# ni.net
KiCad netlist of a schematic drawn in EAGLE
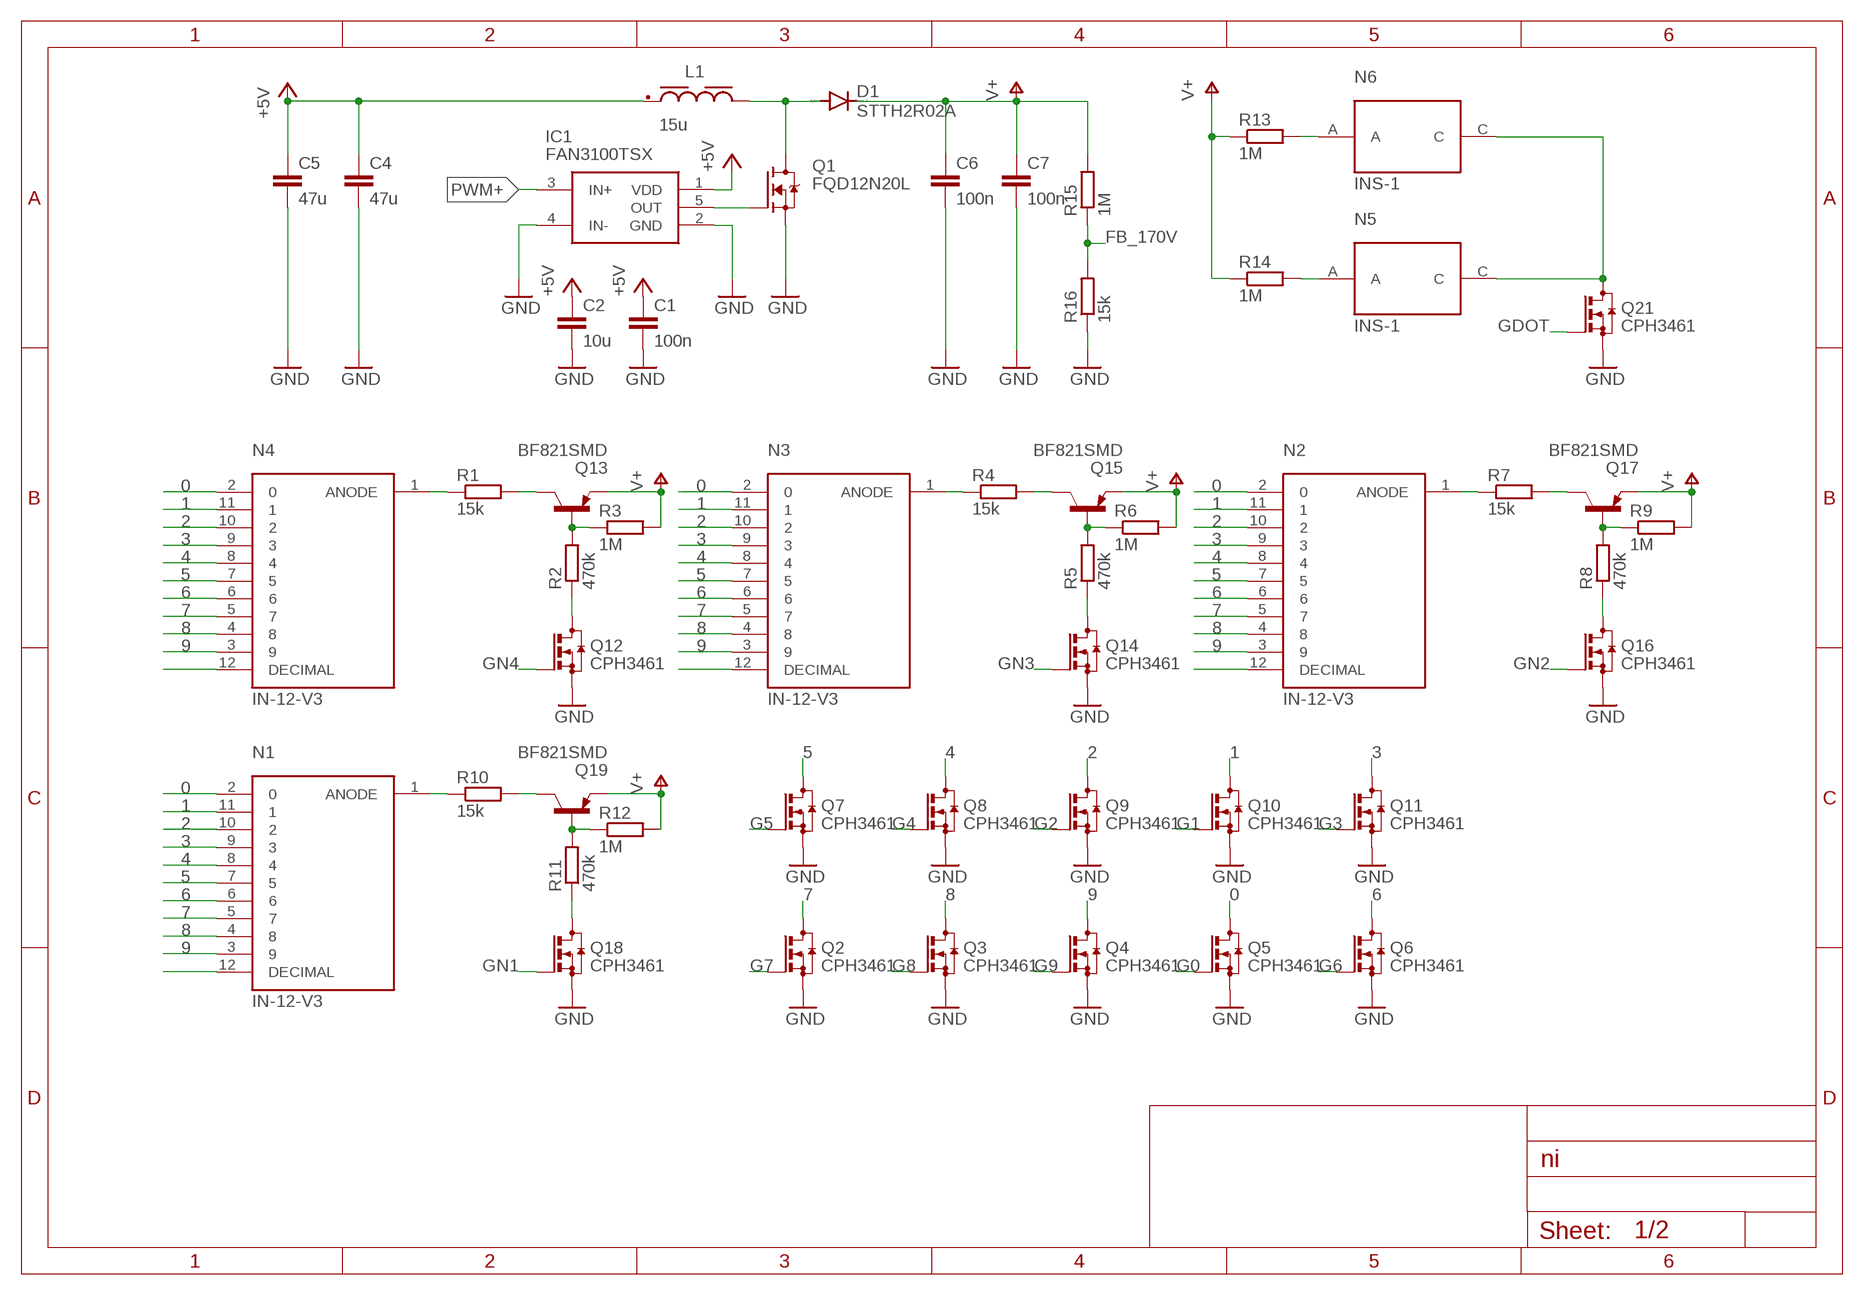
[diagram p0: schematic, sheet 1]
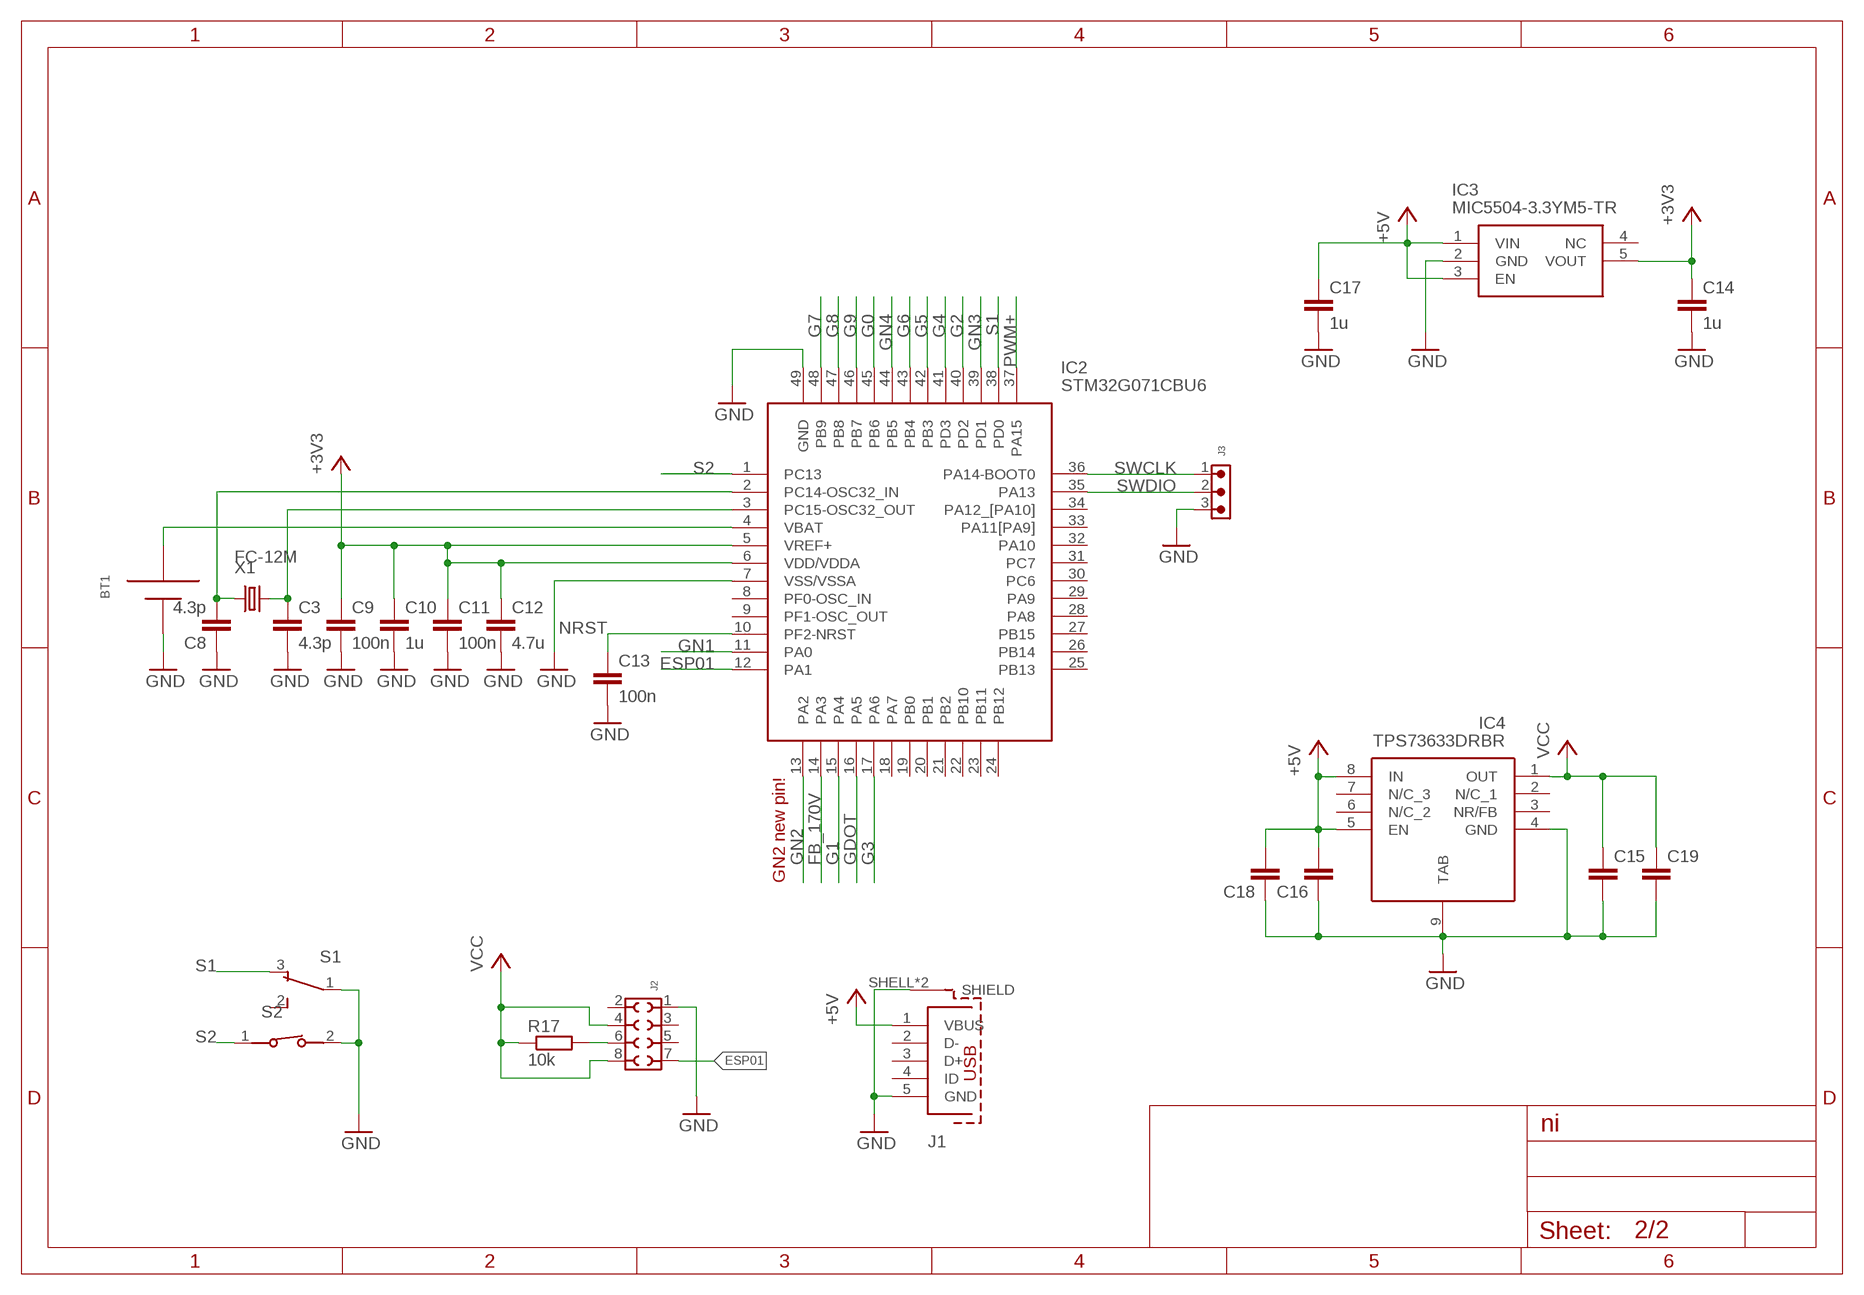
[diagram p1: schematic, sheet 2]

(export (version "E")
  (design (tool "Eeschema 10.0.6"))
  (components
    (comp (ref "C1")
      (value "100n")
      (footprint "eagle-import:C0402")
      (libsource (lib "eagle-import") (part "C-EUC0402"))
    )
    (comp (ref "C2")
      (value "10u")
      (footprint "eagle-import:C1206")
      (libsource (lib "eagle-import") (part "C-EUC1206"))
    )
    (comp (ref "C4")
      (value "47u")
      (footprint "eagle-import:C1206")
      (libsource (lib "eagle-import") (part "C-EUC1206"))
    )
    (comp (ref "C5")
      (value "47u")
      (footprint "eagle-import:C1206")
      (libsource (lib "eagle-import") (part "C-EUC1206"))
    )
    (comp (ref "C6")
      (value "100n")
      (footprint "eagle-import:C1812")
      (libsource (lib "eagle-import") (part "C-EUC1812"))
    )
    (comp (ref "C7")
      (value "100n")
      (footprint "eagle-import:C1812")
      (libsource (lib "eagle-import") (part "C-EUC1812"))
    )
    (comp (ref "D1")
      (value "STTH2R02A")
      (footprint "eagle-import:DO214AC")
      (libsource (lib "eagle-import") (part "DIODE-DO214AC"))
    )
    (comp (ref "IC1")
      (value "FAN3100TSX")
      (footprint "eagle-import:SOT95P280X145-5N")
      (fields (field (name "MOUSER_PART_NUMBER") "512-FAN3100TSX"))
      (libsource (lib "eagle-import") (part "FAN3100TSX"))
    )
    (comp (ref "L1")
      (value "15u")
      (footprint "eagle-import:WE-LQS_5040")
      (libsource (lib "eagle-import") (part "WE-LQS_5040_74404054150"))
    )
    (comp (ref "N1")
      (value "IN-12-V3")
      (footprint "eagle-import:IN-12")
      (libsource (lib "eagle-import") (part "IN-12-V3"))
    )
    (comp (ref "N2")
      (value "IN-12-V3")
      (footprint "eagle-import:IN-12")
      (libsource (lib "eagle-import") (part "IN-12-V3"))
    )
    (comp (ref "N3")
      (value "IN-12-V3")
      (footprint "eagle-import:IN-12")
      (libsource (lib "eagle-import") (part "IN-12-V3"))
    )
    (comp (ref "N4")
      (value "IN-12-V3")
      (footprint "eagle-import:IN-12")
      (libsource (lib "eagle-import") (part "IN-12-V3"))
    )
    (comp (ref "N5")
      (value "INS-1")
      (footprint "eagle-import:INS-1")
      (libsource (lib "eagle-import") (part "INS-1"))
    )
    (comp (ref "N6")
      (value "INS-1")
      (footprint "eagle-import:INS-1")
      (libsource (lib "eagle-import") (part "INS-1"))
    )
    (comp (ref "Q1")
      (value "FQD12N20L")
      (footprint "eagle-import:TO229P990X240-3N")
      (libsource (lib "eagle-import") (part "FQD12N20L"))
    )
    (comp (ref "Q2")
      (value "CPH3461")
      (footprint "eagle-import:SOT23")
      (libsource (lib "eagle-import") (part "BSS123"))
    )
    (comp (ref "Q3")
      (value "CPH3461")
      (footprint "eagle-import:SOT23")
      (libsource (lib "eagle-import") (part "BSS123"))
    )
    (comp (ref "Q4")
      (value "CPH3461")
      (footprint "eagle-import:SOT23")
      (libsource (lib "eagle-import") (part "BSS123"))
    )
    (comp (ref "Q5")
      (value "CPH3461")
      (footprint "eagle-import:SOT23")
      (libsource (lib "eagle-import") (part "BSS123"))
    )
    (comp (ref "Q6")
      (value "CPH3461")
      (footprint "eagle-import:SOT23")
      (libsource (lib "eagle-import") (part "BSS123"))
    )
    (comp (ref "Q7")
      (value "CPH3461")
      (footprint "eagle-import:SOT23")
      (libsource (lib "eagle-import") (part "BSS123"))
    )
    (comp (ref "Q8")
      (value "CPH3461")
      (footprint "eagle-import:SOT23")
      (libsource (lib "eagle-import") (part "BSS123"))
    )
    (comp (ref "Q9")
      (value "CPH3461")
      (footprint "eagle-import:SOT23")
      (libsource (lib "eagle-import") (part "BSS123"))
    )
    (comp (ref "Q10")
      (value "CPH3461")
      (footprint "eagle-import:SOT23")
      (libsource (lib "eagle-import") (part "BSS123"))
    )
    (comp (ref "Q11")
      (value "CPH3461")
      (footprint "eagle-import:SOT23")
      (libsource (lib "eagle-import") (part "BSS123"))
    )
    (comp (ref "Q12")
      (value "CPH3461")
      (footprint "eagle-import:SOT23")
      (libsource (lib "eagle-import") (part "BSS123"))
    )
    (comp (ref "Q13")
      (value "BF821SMD")
      (footprint "eagle-import:SOT23-BEC")
      (libsource (lib "eagle-import") (part "BF821SMD"))
    )
    (comp (ref "Q14")
      (value "CPH3461")
      (footprint "eagle-import:SOT23")
      (libsource (lib "eagle-import") (part "BSS123"))
    )
    (comp (ref "Q15")
      (value "BF821SMD")
      (footprint "eagle-import:SOT23-BEC")
      (libsource (lib "eagle-import") (part "BF821SMD"))
    )
    (comp (ref "Q16")
      (value "CPH3461")
      (footprint "eagle-import:SOT23")
      (libsource (lib "eagle-import") (part "BSS123"))
    )
    (comp (ref "Q17")
      (value "BF821SMD")
      (footprint "eagle-import:SOT23-BEC")
      (libsource (lib "eagle-import") (part "BF821SMD"))
    )
    (comp (ref "Q18")
      (value "CPH3461")
      (footprint "eagle-import:SOT23")
      (libsource (lib "eagle-import") (part "BSS123"))
    )
    (comp (ref "Q19")
      (value "BF821SMD")
      (footprint "eagle-import:SOT23-BEC")
      (libsource (lib "eagle-import") (part "BF821SMD"))
    )
    (comp (ref "Q21")
      (value "CPH3461")
      (footprint "eagle-import:SOT23")
      (libsource (lib "eagle-import") (part "BSS123"))
    )
    (comp (ref "R1")
      (value "15k")
      (footprint "eagle-import:R1206")
      (libsource (lib "eagle-import") (part "R-EU_R1206"))
    )
    (comp (ref "R2")
      (value "470k")
      (footprint "eagle-import:R1206")
      (libsource (lib "eagle-import") (part "R-EU_R1206"))
    )
    (comp (ref "R3")
      (value "1M")
      (footprint "eagle-import:R1206")
      (libsource (lib "eagle-import") (part "R-EU_R1206"))
    )
    (comp (ref "R4")
      (value "15k")
      (footprint "eagle-import:R1206")
      (libsource (lib "eagle-import") (part "R-EU_R1206"))
    )
    (comp (ref "R5")
      (value "470k")
      (footprint "eagle-import:R1206")
      (libsource (lib "eagle-import") (part "R-EU_R1206"))
    )
    (comp (ref "R6")
      (value "1M")
      (footprint "eagle-import:R1206")
      (libsource (lib "eagle-import") (part "R-EU_R1206"))
    )
    (comp (ref "R7")
      (value "15k")
      (footprint "eagle-import:R1206")
      (libsource (lib "eagle-import") (part "R-EU_R1206"))
    )
    (comp (ref "R8")
      (value "470k")
      (footprint "eagle-import:R1206")
      (libsource (lib "eagle-import") (part "R-EU_R1206"))
    )
    (comp (ref "R9")
      (value "1M")
      (footprint "eagle-import:R1206")
      (libsource (lib "eagle-import") (part "R-EU_R1206"))
    )
    (comp (ref "R10")
      (value "15k")
      (footprint "eagle-import:R1206")
      (libsource (lib "eagle-import") (part "R-EU_R1206"))
    )
    (comp (ref "R11")
      (value "470k")
      (footprint "eagle-import:R1206")
      (libsource (lib "eagle-import") (part "R-EU_R1206"))
    )
    (comp (ref "R12")
      (value "1M")
      (footprint "eagle-import:R1206")
      (libsource (lib "eagle-import") (part "R-EU_R1206"))
    )
    (comp (ref "R13")
      (value "1M")
      (footprint "eagle-import:R2010")
      (libsource (lib "eagle-import") (part "R-EU_R2010"))
    )
    (comp (ref "R14")
      (value "1M")
      (footprint "eagle-import:R2010")
      (libsource (lib "eagle-import") (part "R-EU_R2010"))
    )
    (comp (ref "R15")
      (value "1M")
      (footprint "eagle-import:R1206")
      (libsource (lib "eagle-import") (part "R-EU_R1206"))
    )
    (comp (ref "R16")
      (value "15k")
      (footprint "eagle-import:R0402")
      (libsource (lib "eagle-import") (part "R-EU_R0402"))
    )
    (comp (ref "BT1")
      (value "CR1225FH-LF")
      (footprint "eagle-import:CR1225FH-LF")
      (libsource (lib "eagle-import") (part "CR1225FH-LF"))
    )
    (comp (ref "C3")
      (value "4.3p")
      (footprint "eagle-import:C0402")
      (libsource (lib "eagle-import") (part "C-EUC0402"))
    )
    (comp (ref "C8")
      (value "4.3p")
      (footprint "eagle-import:C0402")
      (libsource (lib "eagle-import") (part "C-EUC0402"))
    )
    (comp (ref "C9")
      (value "100n")
      (footprint "eagle-import:C0402")
      (libsource (lib "eagle-import") (part "C-EUC0402"))
    )
    (comp (ref "C10")
      (value "1u")
      (footprint "eagle-import:C0402")
      (libsource (lib "eagle-import") (part "C-EUC0402"))
    )
    (comp (ref "C11")
      (value "100n")
      (footprint "eagle-import:C0402")
      (libsource (lib "eagle-import") (part "C-EUC0402"))
    )
    (comp (ref "C12")
      (value "4.7u")
      (footprint "eagle-import:C0402")
      (libsource (lib "eagle-import") (part "C-EUC0402"))
    )
    (comp (ref "C13")
      (value "100n")
      (footprint "eagle-import:C0402")
      (libsource (lib "eagle-import") (part "C-EUC0402"))
    )
    (comp (ref "C14")
      (value "1u")
      (footprint "eagle-import:C0402")
      (libsource (lib "eagle-import") (part "C-EUC0402"))
    )
    (comp (ref "C15")
      (value "C-EUC1206")
      (footprint "eagle-import:C1206")
      (libsource (lib "eagle-import") (part "C-EUC1206"))
    )
    (comp (ref "C16")
      (value "C-EUC1206")
      (footprint "eagle-import:C1206")
      (libsource (lib "eagle-import") (part "C-EUC1206"))
    )
    (comp (ref "C17")
      (value "1u")
      (footprint "eagle-import:C0603")
      (libsource (lib "eagle-import") (part "C-EUC0603"))
    )
    (comp (ref "C18")
      (value "C-EUC0603")
      (footprint "eagle-import:C0603")
      (libsource (lib "eagle-import") (part "C-EUC0603"))
    )
    (comp (ref "C19")
      (value "C-EUC0603")
      (footprint "eagle-import:C0603")
      (libsource (lib "eagle-import") (part "C-EUC0603"))
    )
    (comp (ref "IC2")
      (value "STM32G071CBU6")
      (footprint "eagle-import:QFN50P700X700X60-49N")
      (fields (field (name "MOUSER_PART_NUMBER") "511-STM32G071CBU6"))
      (libsource (lib "eagle-import") (part "STM32G071CBU6"))
    )
    (comp (ref "IC3")
      (value "MIC5504-3.3YM5-TR")
      (footprint "eagle-import:SOT95P280X145-5N")
      (fields
        (field (name "MOUSER_PART_NUMBER") "998-MIC5504-3.3YM5TR")
        (field (name "RS_PART_NUMBER") "9113332P")
      )
      (libsource (lib "eagle-import") (part "MIC5504-3.3YM5-TR"))
    )
    (comp (ref "IC4")
      (value "TPS73633DRBR")
      (footprint "eagle-import:SON65P300X300X100-9N")
      (fields (field (name "MOUSER_PART_NUMBER") "595-TPS73633DRBR"))
      (libsource (lib "eagle-import") (part "TPS73633DRBR"))
    )
    (comp (ref "J1")
      (value "614105150721")
      (footprint "eagle-import:614105150721")
      (libsource (lib "eagle-import") (part "614105150721"))
    )
    (comp (ref "J2")
      (value "6100XX21821_61000821821")
      (footprint "eagle-import:61000821821")
      (libsource (lib "eagle-import") (part "6100XX21821_61000821821"))
    )
    (comp (ref "J3")
      (value "OWN_3PIN")
      (footprint "eagle-import:OWN-3PIN")
      (libsource (lib "eagle-import") (part "OWN_3PIN"))
    )
    (comp (ref "R17")
      (value "10k")
      (footprint "eagle-import:R0402")
      (libsource (lib "eagle-import") (part "R-EU_R0402"))
    )
    (comp (ref "S1")
      (value "450301014042")
      (footprint "eagle-import:450301014042")
      (libsource (lib "eagle-import") (part "450301014042"))
    )
    (comp (ref "S2")
      (value "434121050816")
      (footprint "eagle-import:434121050816")
      (libsource (lib "eagle-import") (part "434121050816"))
    )
    (comp (ref "X1")
      (value "FC-12M")
      (footprint "eagle-import:FC-12M")
      (libsource (lib "eagle-import") (part "FC-12M"))
    )
  )
  (nets
    (net (code "1") (name "+3V3") (class "Default")
      (node (ref "C10") (pin "1") (pinfunction "1_1") (pintype "passive"))
      (node (ref "C11") (pin "1") (pinfunction "1_1") (pintype "passive"))
      (node (ref "C12") (pin "1") (pinfunction "1_1") (pintype "passive"))
      (node (ref "C14") (pin "1") (pinfunction "1_1") (pintype "passive"))
      (node (ref "C9") (pin "1") (pinfunction "1_1") (pintype "passive"))
      (node (ref "IC2") (pin "5") (pinfunction "VREF+_5") (pintype "bidirectional"))
      (node (ref "IC2") (pin "6") (pinfunction "VDD/VDDA_6") (pintype "bidirectional"))
      (node (ref "IC3") (pin "5") (pinfunction "VOUT_5") (pintype "bidirectional"))
    )
    (net (code "2") (name "+5V") (class "Default")
      (node (ref "C1") (pin "1") (pinfunction "1_1") (pintype "passive"))
      (node (ref "C16") (pin "2") (pinfunction "2_2") (pintype "passive"))
      (node (ref "C17") (pin "1") (pinfunction "1_1") (pintype "passive"))
      (node (ref "C18") (pin "2") (pinfunction "2_2") (pintype "passive"))
      (node (ref "C2") (pin "1") (pinfunction "1_1") (pintype "passive"))
      (node (ref "C4") (pin "1") (pinfunction "1_1") (pintype "passive"))
      (node (ref "C5") (pin "1") (pinfunction "1_1") (pintype "passive"))
      (node (ref "IC1") (pin "1") (pinfunction "VDD_1") (pintype "bidirectional"))
      (node (ref "IC3") (pin "1") (pinfunction "VIN_1") (pintype "bidirectional"))
      (node (ref "IC3") (pin "3") (pinfunction "EN_3") (pintype "bidirectional"))
      (node (ref "IC4") (pin "5") (pinfunction "EN_5") (pintype "bidirectional"))
      (node (ref "IC4") (pin "8") (pinfunction "IN_8") (pintype "input"))
      (node (ref "J1") (pin "1") (pinfunction "VBUS_1") (pintype "passive"))
      (node (ref "L1") (pin "1") (pinfunction "1_1") (pintype "passive"))
    )
    (net (code "3") (name "0") (class "Default")
      (node (ref "N1") (pin "2") (pinfunction "0_2") (pintype "bidirectional"))
      (node (ref "N2") (pin "2") (pinfunction "0_2") (pintype "bidirectional"))
      (node (ref "N3") (pin "2") (pinfunction "0_2") (pintype "bidirectional"))
      (node (ref "N4") (pin "2") (pinfunction "0_2") (pintype "bidirectional"))
      (node (ref "Q5") (pin "3") (pinfunction "D_3") (pintype "passive"))
    )
    (net (code "4") (name "1") (class "Default")
      (node (ref "N1") (pin "11") (pinfunction "1_11") (pintype "bidirectional"))
      (node (ref "N2") (pin "11") (pinfunction "1_11") (pintype "bidirectional"))
      (node (ref "N3") (pin "11") (pinfunction "1_11") (pintype "bidirectional"))
      (node (ref "N4") (pin "11") (pinfunction "1_11") (pintype "bidirectional"))
      (node (ref "Q10") (pin "3") (pinfunction "D_3") (pintype "passive"))
    )
    (net (code "5") (name "2") (class "Default")
      (node (ref "N1") (pin "10") (pinfunction "2_10") (pintype "bidirectional"))
      (node (ref "N2") (pin "10") (pinfunction "2_10") (pintype "bidirectional"))
      (node (ref "N3") (pin "10") (pinfunction "2_10") (pintype "bidirectional"))
      (node (ref "N4") (pin "10") (pinfunction "2_10") (pintype "bidirectional"))
      (node (ref "Q9") (pin "3") (pinfunction "D_3") (pintype "passive"))
    )
    (net (code "6") (name "3") (class "Default")
      (node (ref "N1") (pin "9") (pinfunction "3_9") (pintype "bidirectional"))
      (node (ref "N2") (pin "9") (pinfunction "3_9") (pintype "bidirectional"))
      (node (ref "N3") (pin "9") (pinfunction "3_9") (pintype "bidirectional"))
      (node (ref "N4") (pin "9") (pinfunction "3_9") (pintype "bidirectional"))
      (node (ref "Q11") (pin "3") (pinfunction "D_3") (pintype "passive"))
    )
    (net (code "7") (name "4") (class "Default")
      (node (ref "N1") (pin "8") (pinfunction "4_8") (pintype "bidirectional"))
      (node (ref "N2") (pin "8") (pinfunction "4_8") (pintype "bidirectional"))
      (node (ref "N3") (pin "8") (pinfunction "4_8") (pintype "bidirectional"))
      (node (ref "N4") (pin "8") (pinfunction "4_8") (pintype "bidirectional"))
      (node (ref "Q8") (pin "3") (pinfunction "D_3") (pintype "passive"))
    )
    (net (code "8") (name "5") (class "Default")
      (node (ref "N1") (pin "7") (pinfunction "5_7") (pintype "bidirectional"))
      (node (ref "N2") (pin "7") (pinfunction "5_7") (pintype "bidirectional"))
      (node (ref "N3") (pin "7") (pinfunction "5_7") (pintype "bidirectional"))
      (node (ref "N4") (pin "7") (pinfunction "5_7") (pintype "bidirectional"))
      (node (ref "Q7") (pin "3") (pinfunction "D_3") (pintype "passive"))
    )
    (net (code "9") (name "6") (class "Default")
      (node (ref "N1") (pin "6") (pinfunction "6_6") (pintype "bidirectional"))
      (node (ref "N2") (pin "6") (pinfunction "6_6") (pintype "bidirectional"))
      (node (ref "N3") (pin "6") (pinfunction "6_6") (pintype "bidirectional"))
      (node (ref "N4") (pin "6") (pinfunction "6_6") (pintype "bidirectional"))
      (node (ref "Q6") (pin "3") (pinfunction "D_3") (pintype "passive"))
    )
    (net (code "10") (name "7") (class "Default")
      (node (ref "N1") (pin "5") (pinfunction "7_5") (pintype "bidirectional"))
      (node (ref "N2") (pin "5") (pinfunction "7_5") (pintype "bidirectional"))
      (node (ref "N3") (pin "5") (pinfunction "7_5") (pintype "bidirectional"))
      (node (ref "N4") (pin "5") (pinfunction "7_5") (pintype "bidirectional"))
      (node (ref "Q2") (pin "3") (pinfunction "D_3") (pintype "passive"))
    )
    (net (code "11") (name "8") (class "Default")
      (node (ref "N1") (pin "4") (pinfunction "8_4") (pintype "bidirectional"))
      (node (ref "N2") (pin "4") (pinfunction "8_4") (pintype "bidirectional"))
      (node (ref "N3") (pin "4") (pinfunction "8_4") (pintype "bidirectional"))
      (node (ref "N4") (pin "4") (pinfunction "8_4") (pintype "bidirectional"))
      (node (ref "Q3") (pin "3") (pinfunction "D_3") (pintype "passive"))
    )
    (net (code "12") (name "9") (class "Default")
      (node (ref "N1") (pin "3") (pinfunction "9_3") (pintype "bidirectional"))
      (node (ref "N2") (pin "3") (pinfunction "9_3") (pintype "bidirectional"))
      (node (ref "N3") (pin "3") (pinfunction "9_3") (pintype "bidirectional"))
      (node (ref "N4") (pin "3") (pinfunction "9_3") (pintype "bidirectional"))
      (node (ref "Q4") (pin "3") (pinfunction "D_3") (pintype "passive"))
    )
    (net (code "13") (name "ESP01") (class "Default")
      (node (ref "IC2") (pin "12") (pinfunction "PA1_12") (pintype "bidirectional"))
      (node (ref "J2") (pin "7") (pinfunction "7_7") (pintype "passive"))
    )
    (net (code "14") (name "FB_170V") (class "Default")
      (node (ref "IC2") (pin "14") (pinfunction "PA3_14") (pintype "bidirectional"))
      (node (ref "R15") (pin "1") (pinfunction "1_1") (pintype "passive"))
      (node (ref "R16") (pin "2") (pinfunction "2_2") (pintype "passive"))
    )
    (net (code "15") (name "G0") (class "Default")
      (node (ref "IC2") (pin "45") (pinfunction "PB6_45") (pintype "bidirectional"))
      (node (ref "Q5") (pin "1") (pinfunction "G_1") (pintype "passive"))
    )
    (net (code "16") (name "G1") (class "Default")
      (node (ref "IC2") (pin "15") (pinfunction "PA4_15") (pintype "bidirectional"))
      (node (ref "Q10") (pin "1") (pinfunction "G_1") (pintype "passive"))
    )
    (net (code "17") (name "G2") (class "Default")
      (node (ref "IC2") (pin "40") (pinfunction "PD2_40") (pintype "bidirectional"))
      (node (ref "Q9") (pin "1") (pinfunction "G_1") (pintype "passive"))
    )
    (net (code "18") (name "G3") (class "Default")
      (node (ref "IC2") (pin "17") (pinfunction "PA6_17") (pintype "bidirectional"))
      (node (ref "Q11") (pin "1") (pinfunction "G_1") (pintype "passive"))
    )
    (net (code "19") (name "G4") (class "Default")
      (node (ref "IC2") (pin "41") (pinfunction "PD3_41") (pintype "bidirectional"))
      (node (ref "Q8") (pin "1") (pinfunction "G_1") (pintype "passive"))
    )
    (net (code "20") (name "G5") (class "Default")
      (node (ref "IC2") (pin "42") (pinfunction "PB3_42") (pintype "bidirectional"))
      (node (ref "Q7") (pin "1") (pinfunction "G_1") (pintype "passive"))
    )
    (net (code "21") (name "G6") (class "Default")
      (node (ref "IC2") (pin "43") (pinfunction "PB4_43") (pintype "bidirectional"))
      (node (ref "Q6") (pin "1") (pinfunction "G_1") (pintype "passive"))
    )
    (net (code "22") (name "G7") (class "Default")
      (node (ref "IC2") (pin "48") (pinfunction "PB9_48") (pintype "bidirectional"))
      (node (ref "Q2") (pin "1") (pinfunction "G_1") (pintype "passive"))
    )
    (net (code "23") (name "G8") (class "Default")
      (node (ref "IC2") (pin "47") (pinfunction "PB8_47") (pintype "bidirectional"))
      (node (ref "Q3") (pin "1") (pinfunction "G_1") (pintype "passive"))
    )
    (net (code "24") (name "G9") (class "Default")
      (node (ref "IC2") (pin "46") (pinfunction "PB7_46") (pintype "bidirectional"))
      (node (ref "Q4") (pin "1") (pinfunction "G_1") (pintype "passive"))
    )
    (net (code "25") (name "GDOT") (class "Default")
      (node (ref "IC2") (pin "16") (pinfunction "PA5_16") (pintype "bidirectional"))
      (node (ref "Q21") (pin "1") (pinfunction "G_1") (pintype "passive"))
    )
    (net (code "26") (name "GN1") (class "Default")
      (node (ref "IC2") (pin "11") (pinfunction "PA0_11") (pintype "bidirectional"))
      (node (ref "Q18") (pin "1") (pinfunction "G_1") (pintype "passive"))
    )
    (net (code "27") (name "GN2") (class "Default")
      (node (ref "IC2") (pin "13") (pinfunction "PA2_13") (pintype "bidirectional"))
      (node (ref "Q16") (pin "1") (pinfunction "G_1") (pintype "passive"))
    )
    (net (code "28") (name "GN3") (class "Default")
      (node (ref "IC2") (pin "39") (pinfunction "PD1_39") (pintype "bidirectional"))
      (node (ref "Q14") (pin "1") (pinfunction "G_1") (pintype "passive"))
    )
    (net (code "29") (name "GN4") (class "Default")
      (node (ref "IC2") (pin "44") (pinfunction "PB5_44") (pintype "bidirectional"))
      (node (ref "Q12") (pin "1") (pinfunction "G_1") (pintype "passive"))
    )
    (net (code "30") (name "GND") (class "Default")
      (node (ref "BT1") (pin "-") (pinfunction "-_-") (pintype "output"))
      (node (ref "C1") (pin "2") (pinfunction "2_2") (pintype "passive"))
      (node (ref "C10") (pin "2") (pinfunction "2_2") (pintype "passive"))
      (node (ref "C11") (pin "2") (pinfunction "2_2") (pintype "passive"))
      (node (ref "C12") (pin "2") (pinfunction "2_2") (pintype "passive"))
      (node (ref "C13") (pin "2") (pinfunction "2_2") (pintype "passive"))
      (node (ref "C14") (pin "2") (pinfunction "2_2") (pintype "passive"))
      (node (ref "C15") (pin "2") (pinfunction "2_2") (pintype "passive"))
      (node (ref "C16") (pin "1") (pinfunction "1_1") (pintype "passive"))
      (node (ref "C17") (pin "2") (pinfunction "2_2") (pintype "passive"))
      (node (ref "C18") (pin "1") (pinfunction "1_1") (pintype "passive"))
      (node (ref "C19") (pin "2") (pinfunction "2_2") (pintype "passive"))
      (node (ref "C2") (pin "2") (pinfunction "2_2") (pintype "passive"))
      (node (ref "C3") (pin "2") (pinfunction "2_2") (pintype "passive"))
      (node (ref "C4") (pin "2") (pinfunction "2_2") (pintype "passive"))
      (node (ref "C5") (pin "2") (pinfunction "2_2") (pintype "passive"))
      (node (ref "C6") (pin "2") (pinfunction "2_2") (pintype "passive"))
      (node (ref "C7") (pin "2") (pinfunction "2_2") (pintype "passive"))
      (node (ref "C8") (pin "1") (pinfunction "1_1") (pintype "passive"))
      (node (ref "C9") (pin "2") (pinfunction "2_2") (pintype "passive"))
      (node (ref "IC1") (pin "2") (pinfunction "GND_2") (pintype "bidirectional"))
      (node (ref "IC1") (pin "4") (pinfunction "IN-_4") (pintype "bidirectional"))
      (node (ref "IC2") (pin "49") (pinfunction "GND_49") (pintype "bidirectional"))
      (node (ref "IC2") (pin "7") (pinfunction "VSS/VSSA_7") (pintype "bidirectional"))
      (node (ref "IC3") (pin "2") (pinfunction "GND_2") (pintype "bidirectional"))
      (node (ref "IC4") (pin "4") (pinfunction "GND_4") (pintype "power_in"))
      (node (ref "IC4") (pin "9") (pinfunction "TAB_9") (pintype "bidirectional"))
      (node (ref "J1") (pin "5") (pinfunction "GND_5") (pintype "passive"))
      (node (ref "J1") (pin "SHELL") (pinfunction "SHIELD_SHELL") (pintype "passive"))
      (node (ref "J1") (pin "SHELL1") (pinfunction "SHIELD_SHELL1") (pintype "passive"))
      (node (ref "J2") (pin "1") (pinfunction "1_1") (pintype "passive"))
      (node (ref "J3") (pin "3") (pinfunction "3_3") (pintype "passive"))
      (node (ref "Q1") (pin "2") (pinfunction "S_2") (pintype "passive"))
      (node (ref "Q10") (pin "2") (pinfunction "S_2") (pintype "passive"))
      (node (ref "Q11") (pin "2") (pinfunction "S_2") (pintype "passive"))
      (node (ref "Q12") (pin "2") (pinfunction "S_2") (pintype "passive"))
      (node (ref "Q14") (pin "2") (pinfunction "S_2") (pintype "passive"))
      (node (ref "Q16") (pin "2") (pinfunction "S_2") (pintype "passive"))
      (node (ref "Q18") (pin "2") (pinfunction "S_2") (pintype "passive"))
      (node (ref "Q2") (pin "2") (pinfunction "S_2") (pintype "passive"))
      (node (ref "Q21") (pin "2") (pinfunction "S_2") (pintype "passive"))
      (node (ref "Q3") (pin "2") (pinfunction "S_2") (pintype "passive"))
      (node (ref "Q4") (pin "2") (pinfunction "S_2") (pintype "passive"))
      (node (ref "Q5") (pin "2") (pinfunction "S_2") (pintype "passive"))
      (node (ref "Q6") (pin "2") (pinfunction "S_2") (pintype "passive"))
      (node (ref "Q7") (pin "2") (pinfunction "S_2") (pintype "passive"))
      (node (ref "Q8") (pin "2") (pinfunction "S_2") (pintype "passive"))
      (node (ref "Q9") (pin "2") (pinfunction "S_2") (pintype "passive"))
      (node (ref "R16") (pin "1") (pinfunction "1_1") (pintype "passive"))
      (node (ref "S1") (pin "1") (pinfunction "1_1") (pintype "passive"))
      (node (ref "S2") (pin "2") (pinfunction "2_2") (pintype "passive"))
    )
    (net (code "31") (name "NRST") (class "Default")
      (node (ref "C13") (pin "1") (pinfunction "1_1") (pintype "passive"))
      (node (ref "IC2") (pin "10") (pinfunction "PF2-NRST_10") (pintype "bidirectional"))
    )
    (net (code "32") (name "Net-(IC1-OUT)") (class "Default")
      (node (ref "IC1") (pin "5") (pinfunction "OUT_5") (pintype "bidirectional"))
      (node (ref "Q1") (pin "1") (pinfunction "G_1") (pintype "passive"))
    )
    (net (code "33") (name "Net-(IC2-PC14-OSC32_IN)") (class "Default")
      (node (ref "C8") (pin "2") (pinfunction "2_2") (pintype "passive"))
      (node (ref "IC2") (pin "2") (pinfunction "PC14-OSC32_IN_2") (pintype "bidirectional"))
      (node (ref "X1") (pin "1") (pinfunction "1_1") (pintype "passive"))
    )
    (net (code "34") (name "Net-(IC2-PC15-OSC32_OUT)") (class "Default")
      (node (ref "C3") (pin "1") (pinfunction "1_1") (pintype "passive"))
      (node (ref "IC2") (pin "3") (pinfunction "PC15-OSC32_OUT_3") (pintype "bidirectional"))
      (node (ref "X1") (pin "2") (pinfunction "2_2") (pintype "passive"))
    )
    (net (code "35") (name "Net-(IC2-VBAT)") (class "Default")
      (node (ref "BT1") (pin "+") (pinfunction "+_+") (pintype "output"))
      (node (ref "IC2") (pin "4") (pinfunction "VBAT_4") (pintype "bidirectional"))
    )
    (net (code "36") (name "Net-(J2-Pad6)") (class "Default")
      (node (ref "J2") (pin "6") (pinfunction "6_6") (pintype "passive"))
      (node (ref "R17") (pin "2") (pinfunction "2_2") (pintype "passive"))
    )
    (net (code "37") (name "Net-(N1-ANODE)") (class "Default")
      (node (ref "N1") (pin "1") (pinfunction "ANODE_1") (pintype "bidirectional"))
      (node (ref "R10") (pin "1") (pinfunction "1_1") (pintype "passive"))
    )
    (net (code "38") (name "Net-(N2-ANODE)") (class "Default")
      (node (ref "N2") (pin "1") (pinfunction "ANODE_1") (pintype "bidirectional"))
      (node (ref "R7") (pin "1") (pinfunction "1_1") (pintype "passive"))
    )
    (net (code "39") (name "Net-(N3-ANODE)") (class "Default")
      (node (ref "N3") (pin "1") (pinfunction "ANODE_1") (pintype "bidirectional"))
      (node (ref "R4") (pin "1") (pinfunction "1_1") (pintype "passive"))
    )
    (net (code "40") (name "Net-(N4-ANODE)") (class "Default")
      (node (ref "N4") (pin "1") (pinfunction "ANODE_1") (pintype "bidirectional"))
      (node (ref "R1") (pin "1") (pinfunction "1_1") (pintype "passive"))
    )
    (net (code "41") (name "Net-(N5-PadA)") (class "Default")
      (node (ref "N5") (pin "A") (pinfunction "A_A") (pintype "bidirectional"))
      (node (ref "R14") (pin "2") (pinfunction "2_2") (pintype "passive"))
    )
    (net (code "42") (name "Net-(N6-PadA)") (class "Default")
      (node (ref "N6") (pin "A") (pinfunction "A_A") (pintype "bidirectional"))
      (node (ref "R13") (pin "2") (pinfunction "2_2") (pintype "passive"))
    )
    (net (code "43") (name "Net-(Q1-D)") (class "Default")
      (node (ref "D1") (pin "A") (pinfunction "A_A") (pintype "passive"))
      (node (ref "L1") (pin "2") (pinfunction "2_2") (pintype "passive"))
      (node (ref "Q1") (pin "3") (pinfunction "D_3") (pintype "passive"))
    )
    (net (code "44") (name "Net-(Q12-D)") (class "Default")
      (node (ref "Q12") (pin "3") (pinfunction "D_3") (pintype "passive"))
      (node (ref "R2") (pin "1") (pinfunction "1_1") (pintype "passive"))
    )
    (net (code "45") (name "Net-(Q13-PadB)") (class "Default")
      (node (ref "Q13") (pin "B") (pinfunction "B_B") (pintype "passive"))
      (node (ref "R2") (pin "2") (pinfunction "2_2") (pintype "passive"))
      (node (ref "R3") (pin "1") (pinfunction "1_1") (pintype "passive"))
    )
    (net (code "46") (name "Net-(Q13-PadC)") (class "Default")
      (node (ref "Q13") (pin "C") (pinfunction "C_C") (pintype "passive"))
      (node (ref "R1") (pin "2") (pinfunction "2_2") (pintype "passive"))
    )
    (net (code "47") (name "Net-(Q14-D)") (class "Default")
      (node (ref "Q14") (pin "3") (pinfunction "D_3") (pintype "passive"))
      (node (ref "R5") (pin "1") (pinfunction "1_1") (pintype "passive"))
    )
    (net (code "48") (name "Net-(Q15-PadB)") (class "Default")
      (node (ref "Q15") (pin "B") (pinfunction "B_B") (pintype "passive"))
      (node (ref "R5") (pin "2") (pinfunction "2_2") (pintype "passive"))
      (node (ref "R6") (pin "1") (pinfunction "1_1") (pintype "passive"))
    )
    (net (code "49") (name "Net-(Q15-PadC)") (class "Default")
      (node (ref "Q15") (pin "C") (pinfunction "C_C") (pintype "passive"))
      (node (ref "R4") (pin "2") (pinfunction "2_2") (pintype "passive"))
    )
    (net (code "50") (name "Net-(Q16-D)") (class "Default")
      (node (ref "Q16") (pin "3") (pinfunction "D_3") (pintype "passive"))
      (node (ref "R8") (pin "1") (pinfunction "1_1") (pintype "passive"))
    )
    (net (code "51") (name "Net-(Q17-PadB)") (class "Default")
      (node (ref "Q17") (pin "B") (pinfunction "B_B") (pintype "passive"))
      (node (ref "R8") (pin "2") (pinfunction "2_2") (pintype "passive"))
      (node (ref "R9") (pin "1") (pinfunction "1_1") (pintype "passive"))
    )
    (net (code "52") (name "Net-(Q17-PadC)") (class "Default")
      (node (ref "Q17") (pin "C") (pinfunction "C_C") (pintype "passive"))
      (node (ref "R7") (pin "2") (pinfunction "2_2") (pintype "passive"))
    )
    (net (code "53") (name "Net-(Q18-D)") (class "Default")
      (node (ref "Q18") (pin "3") (pinfunction "D_3") (pintype "passive"))
      (node (ref "R11") (pin "1") (pinfunction "1_1") (pintype "passive"))
    )
    (net (code "54") (name "Net-(Q19-PadB)") (class "Default")
      (node (ref "Q19") (pin "B") (pinfunction "B_B") (pintype "passive"))
      (node (ref "R11") (pin "2") (pinfunction "2_2") (pintype "passive"))
      (node (ref "R12") (pin "1") (pinfunction "1_1") (pintype "passive"))
    )
    (net (code "55") (name "Net-(Q19-PadC)") (class "Default")
      (node (ref "Q19") (pin "C") (pinfunction "C_C") (pintype "passive"))
      (node (ref "R10") (pin "2") (pinfunction "2_2") (pintype "passive"))
    )
    (net (code "56") (name "Net-(Q21-D)") (class "Default")
      (node (ref "N5") (pin "C") (pinfunction "C_C") (pintype "bidirectional"))
      (node (ref "N6") (pin "C") (pinfunction "C_C") (pintype "bidirectional"))
      (node (ref "Q21") (pin "3") (pinfunction "D_3") (pintype "passive"))
    )
    (net (code "57") (name "PWM+") (class "Default")
      (node (ref "IC1") (pin "3") (pinfunction "IN+_3") (pintype "bidirectional"))
      (node (ref "IC2") (pin "37") (pinfunction "PA15_37") (pintype "bidirectional"))
    )
    (net (code "58") (name "S1") (class "Default")
      (node (ref "IC2") (pin "38") (pinfunction "PD0_38") (pintype "bidirectional"))
      (node (ref "S1") (pin "3") (pinfunction "3_3") (pintype "passive"))
    )
    (net (code "59") (name "S2") (class "Default")
      (node (ref "IC2") (pin "1") (pinfunction "PC13_1") (pintype "bidirectional"))
      (node (ref "S2") (pin "1") (pinfunction "1_1") (pintype "passive"))
    )
    (net (code "60") (name "SWCLK") (class "Default")
      (node (ref "IC2") (pin "36") (pinfunction "PA14-BOOT0_36") (pintype "bidirectional"))
      (node (ref "J3") (pin "1") (pinfunction "1_1") (pintype "passive"))
    )
    (net (code "61") (name "SWDIO") (class "Default")
      (node (ref "IC2") (pin "35") (pinfunction "PA13_35") (pintype "bidirectional"))
      (node (ref "J3") (pin "2") (pinfunction "2_2") (pintype "passive"))
    )
    (net (code "62") (name "V+") (class "Default")
      (node (ref "C6") (pin "1") (pinfunction "1_1") (pintype "passive"))
      (node (ref "C7") (pin "1") (pinfunction "1_1") (pintype "passive"))
      (node (ref "D1") (pin "C") (pinfunction "C_C") (pintype "passive"))
      (node (ref "Q13") (pin "E") (pinfunction "E_E") (pintype "passive"))
      (node (ref "Q15") (pin "E") (pinfunction "E_E") (pintype "passive"))
      (node (ref "Q17") (pin "E") (pinfunction "E_E") (pintype "passive"))
      (node (ref "Q19") (pin "E") (pinfunction "E_E") (pintype "passive"))
      (node (ref "R12") (pin "2") (pinfunction "2_2") (pintype "passive"))
      (node (ref "R13") (pin "1") (pinfunction "1_1") (pintype "passive"))
      (node (ref "R14") (pin "1") (pinfunction "1_1") (pintype "passive"))
      (node (ref "R15") (pin "2") (pinfunction "2_2") (pintype "passive"))
      (node (ref "R3") (pin "2") (pinfunction "2_2") (pintype "passive"))
      (node (ref "R6") (pin "2") (pinfunction "2_2") (pintype "passive"))
      (node (ref "R9") (pin "2") (pinfunction "2_2") (pintype "passive"))
    )
    (net (code "63") (name "VCC") (class "Default")
      (node (ref "C15") (pin "1") (pinfunction "1_1") (pintype "passive"))
      (node (ref "C19") (pin "1") (pinfunction "1_1") (pintype "passive"))
      (node (ref "IC4") (pin "1") (pinfunction "OUT_1") (pintype "output"))
      (node (ref "J2") (pin "4") (pinfunction "4_4") (pintype "passive"))
      (node (ref "J2") (pin "8") (pinfunction "8_8") (pintype "passive"))
      (node (ref "R17") (pin "1") (pinfunction "1_1") (pintype "passive"))
    )
    (net (code "64") (name "unconnected-(IC2-PA7-Pad18)") (class "Default")
      (node (ref "IC2") (pin "18") (pinfunction "PA7_18") (pintype "bidirectional"))
    )
    (net (code "65") (name "unconnected-(IC2-PA8-Pad28)") (class "Default")
      (node (ref "IC2") (pin "28") (pinfunction "PA8_28") (pintype "bidirectional"))
    )
    (net (code "66") (name "unconnected-(IC2-PA9-Pad29)") (class "Default")
      (node (ref "IC2") (pin "29") (pinfunction "PA9_29") (pintype "bidirectional"))
    )
    (net (code "67") (name "unconnected-(IC2-PA10-Pad32)") (class "Default")
      (node (ref "IC2") (pin "32") (pinfunction "PA10_32") (pintype "bidirectional"))
    )
    (net (code "68") (name "unconnected-(IC2-PA11[PA9]-Pad33)") (class "Default")
      (node (ref "IC2") (pin "33") (pinfunction "PA11[PA9]_33") (pintype "bidirectional"))
    )
    (net (code "69") (name "unconnected-(IC2-PA12_[PA10]-Pad34)") (class "Default")
      (node (ref "IC2") (pin "34") (pinfunction "PA12_[PA10]_34") (pintype "bidirectional"))
    )
    (net (code "70") (name "unconnected-(IC2-PB0-Pad19)") (class "Default")
      (node (ref "IC2") (pin "19") (pinfunction "PB0_19") (pintype "bidirectional"))
    )
    (net (code "71") (name "unconnected-(IC2-PB1-Pad20)") (class "Default")
      (node (ref "IC2") (pin "20") (pinfunction "PB1_20") (pintype "bidirectional"))
    )
    (net (code "72") (name "unconnected-(IC2-PB2-Pad21)") (class "Default")
      (node (ref "IC2") (pin "21") (pinfunction "PB2_21") (pintype "bidirectional"))
    )
    (net (code "73") (name "unconnected-(IC2-PB10-Pad22)") (class "Default")
      (node (ref "IC2") (pin "22") (pinfunction "PB10_22") (pintype "bidirectional"))
    )
    (net (code "74") (name "unconnected-(IC2-PB11-Pad23)") (class "Default")
      (node (ref "IC2") (pin "23") (pinfunction "PB11_23") (pintype "bidirectional"))
    )
    (net (code "75") (name "unconnected-(IC2-PB12-Pad24)") (class "Default")
      (node (ref "IC2") (pin "24") (pinfunction "PB12_24") (pintype "bidirectional"))
    )
    (net (code "76") (name "unconnected-(IC2-PB13-Pad25)") (class "Default")
      (node (ref "IC2") (pin "25") (pinfunction "PB13_25") (pintype "bidirectional"))
    )
    (net (code "77") (name "unconnected-(IC2-PB14-Pad26)") (class "Default")
      (node (ref "IC2") (pin "26") (pinfunction "PB14_26") (pintype "bidirectional"))
    )
    (net (code "78") (name "unconnected-(IC2-PB15-Pad27)") (class "Default")
      (node (ref "IC2") (pin "27") (pinfunction "PB15_27") (pintype "bidirectional"))
    )
    (net (code "79") (name "unconnected-(IC2-PC6-Pad30)") (class "Default")
      (node (ref "IC2") (pin "30") (pinfunction "PC6_30") (pintype "bidirectional"))
    )
    (net (code "80") (name "unconnected-(IC2-PC7-Pad31)") (class "Default")
      (node (ref "IC2") (pin "31") (pinfunction "PC7_31") (pintype "bidirectional"))
    )
    (net (code "81") (name "unconnected-(IC2-PF0-OSC_IN-Pad8)") (class "Default")
      (node (ref "IC2") (pin "8") (pinfunction "PF0-OSC_IN_8") (pintype "bidirectional"))
    )
    (net (code "82") (name "unconnected-(IC2-PF1-OSC_OUT-Pad9)") (class "Default")
      (node (ref "IC2") (pin "9") (pinfunction "PF1-OSC_OUT_9") (pintype "bidirectional"))
    )
    (net (code "83") (name "unconnected-(IC3-NC-Pad4)") (class "Default")
      (node (ref "IC3") (pin "4") (pinfunction "NC_4") (pintype "no_connect"))
    )
    (net (code "84") (name "unconnected-(IC4-NR{slash}FB-Pad3)") (class "Default")
      (node (ref "IC4") (pin "3") (pinfunction "NR/FB_3") (pintype "bidirectional"))
    )
    (net (code "85") (name "unconnected-(IC4-N{slash}C_1-Pad2)") (class "Default")
      (node (ref "IC4") (pin "2") (pinfunction "N/C_1_2") (pintype "bidirectional"))
    )
    (net (code "86") (name "unconnected-(IC4-N{slash}C_2-Pad6)") (class "Default")
      (node (ref "IC4") (pin "6") (pinfunction "N/C_2_6") (pintype "bidirectional"))
    )
    (net (code "87") (name "unconnected-(IC4-N{slash}C_3-Pad7)") (class "Default")
      (node (ref "IC4") (pin "7") (pinfunction "N/C_3_7") (pintype "bidirectional"))
    )
    (net (code "88") (name "unconnected-(J1-D+-Pad3)") (class "Default")
      (node (ref "J1") (pin "3") (pinfunction "D+_3") (pintype "passive"))
    )
    (net (code "89") (name "unconnected-(J1-D--Pad2)") (class "Default")
      (node (ref "J1") (pin "2") (pinfunction "D-_2") (pintype "passive"))
    )
    (net (code "90") (name "unconnected-(J1-ID-Pad4)") (class "Default")
      (node (ref "J1") (pin "4") (pinfunction "ID_4") (pintype "passive"))
    )
    (net (code "91") (name "unconnected-(J2-Pad2)") (class "Default")
      (node (ref "J2") (pin "2") (pinfunction "2_2") (pintype "passive"))
    )
    (net (code "92") (name "unconnected-(J2-Pad3)") (class "Default")
      (node (ref "J2") (pin "3") (pinfunction "3_3") (pintype "passive"))
    )
    (net (code "93") (name "unconnected-(J2-Pad5)") (class "Default")
      (node (ref "J2") (pin "5") (pinfunction "5_5") (pintype "passive"))
    )
    (net (code "94") (name "unconnected-(N1-DECIMAL-Pad12)") (class "Default")
      (node (ref "N1") (pin "12") (pinfunction "DECIMAL_12") (pintype "bidirectional"))
    )
    (net (code "95") (name "unconnected-(N2-DECIMAL-Pad12)") (class "Default")
      (node (ref "N2") (pin "12") (pinfunction "DECIMAL_12") (pintype "bidirectional"))
    )
    (net (code "96") (name "unconnected-(N3-DECIMAL-Pad12)") (class "Default")
      (node (ref "N3") (pin "12") (pinfunction "DECIMAL_12") (pintype "bidirectional"))
    )
    (net (code "97") (name "unconnected-(N4-DECIMAL-Pad12)") (class "Default")
      (node (ref "N4") (pin "12") (pinfunction "DECIMAL_12") (pintype "bidirectional"))
    )
    (net (code "98") (name "unconnected-(S1-Pad2)") (class "Default")
      (node (ref "S1") (pin "2") (pinfunction "2_2") (pintype "passive"))
    )
  )
)
